# 0008_h_field_probe_1x3mm.net
KiCad netlist of a schematic drawn in EAGLE
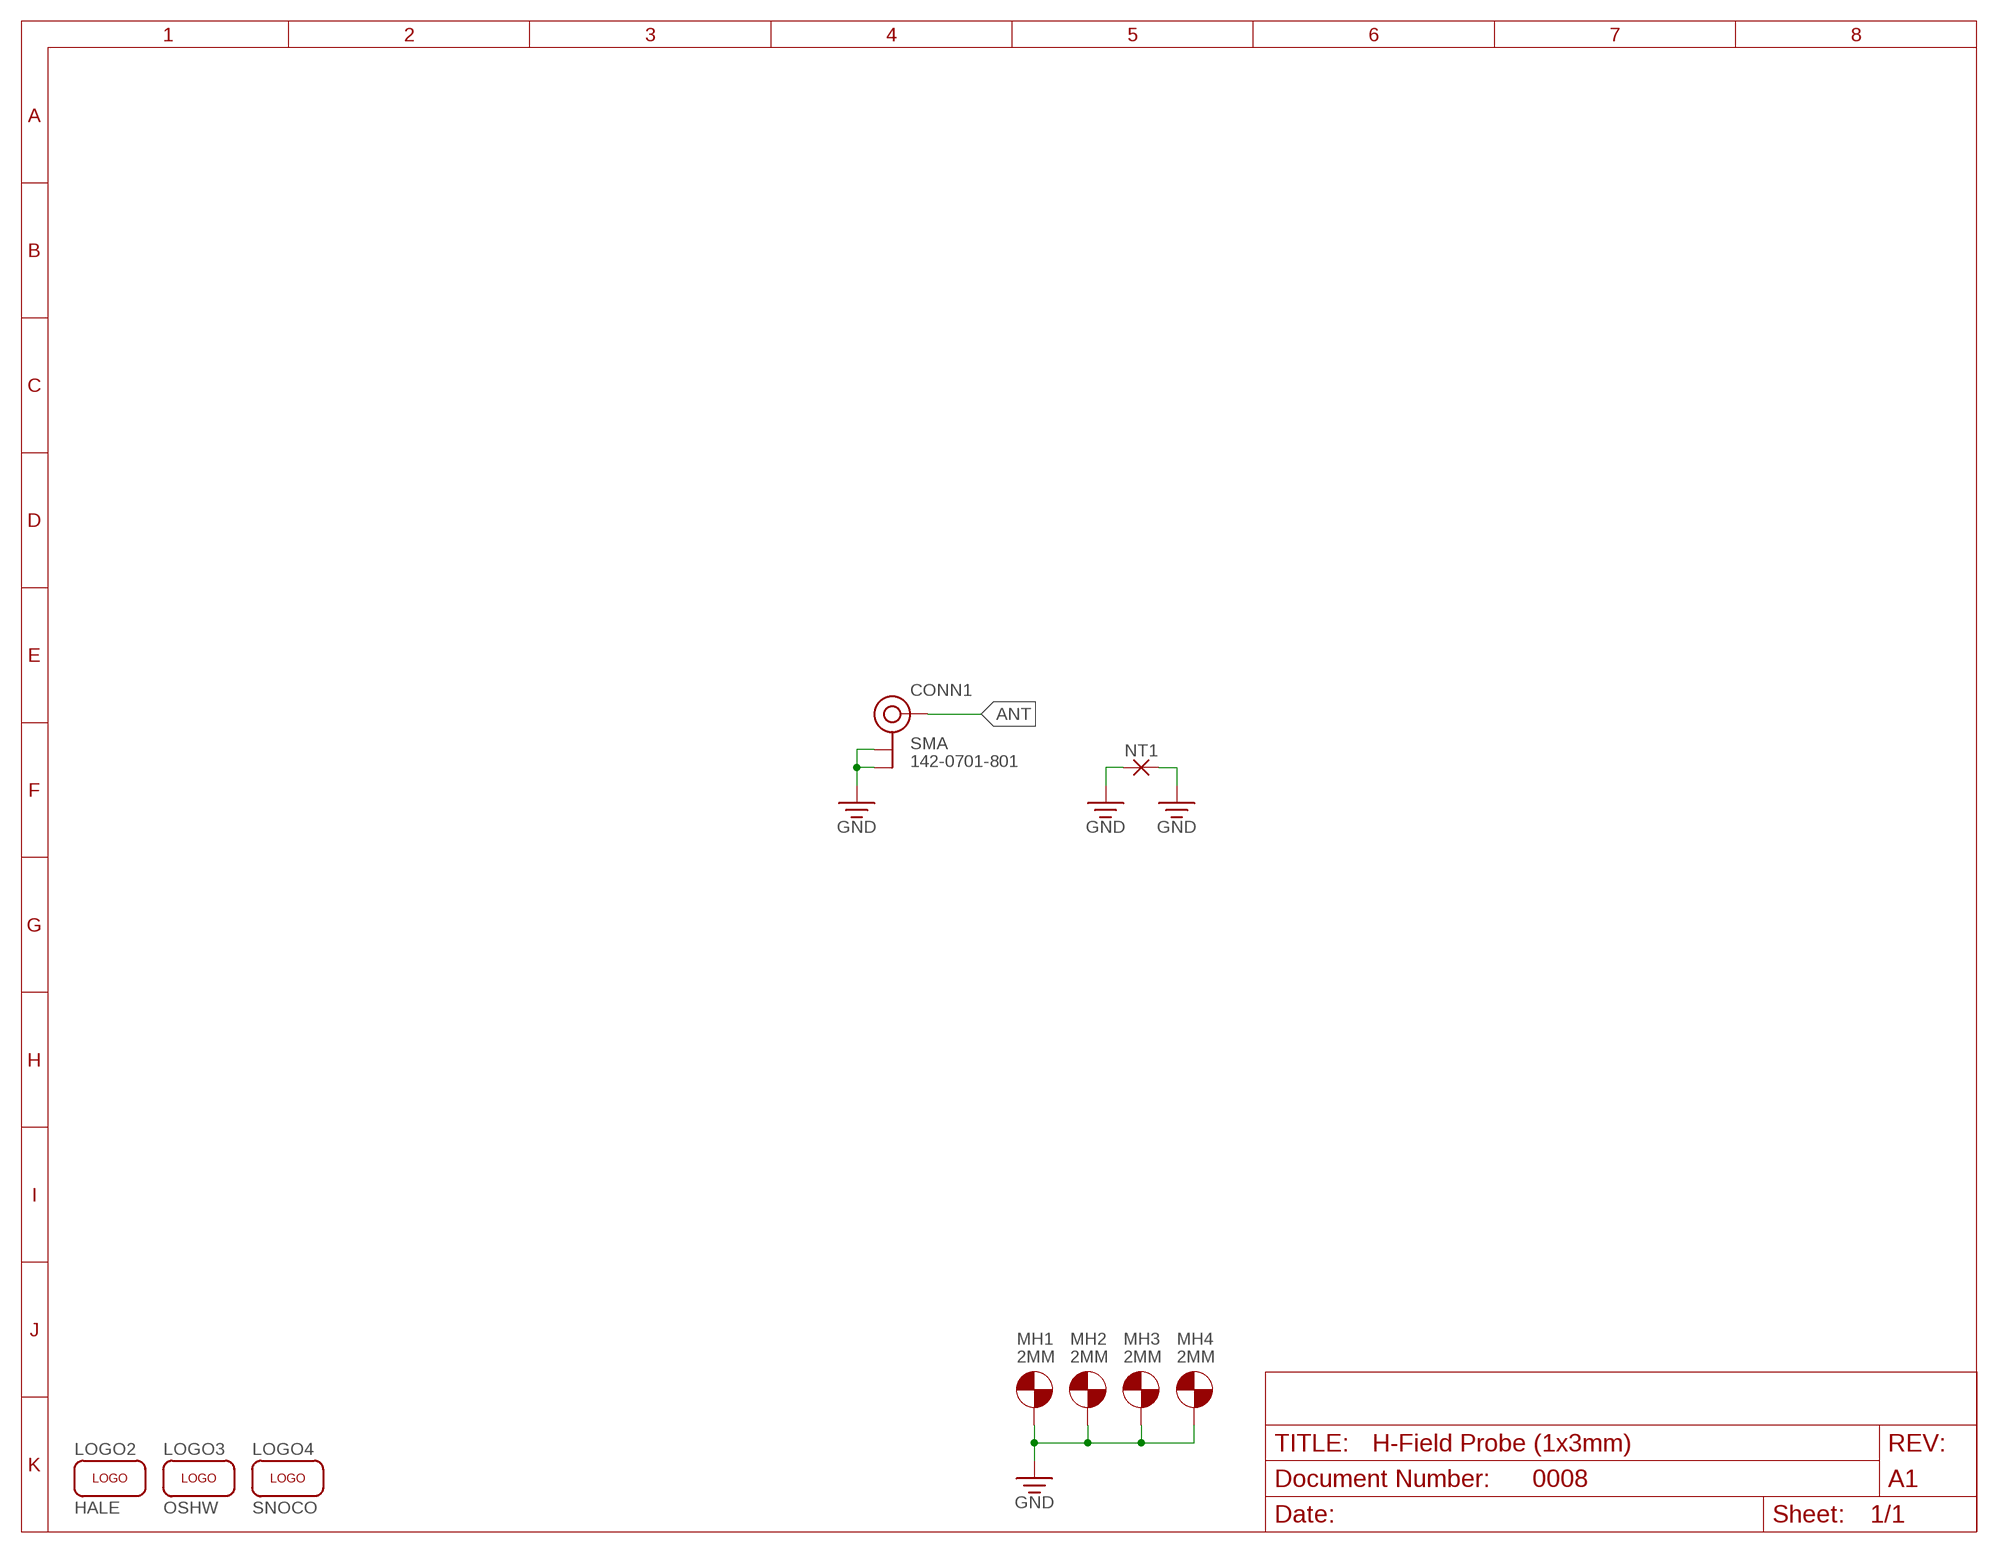
[diagram p0: schematic, sheet 1]

(export (version "E")
  (design (tool "Eeschema 10.0.6"))
  (components
    (comp (ref "CONN1")
      (value "SMA")
      (footprint "eagle-import:SMA-142-0701-801")
      (fields (field (name "MFG") "Cinch Connectivity Solutions Johnson"))
      (libsource (lib "eagle-import") (part "COAX-CONNECTOR-EDGE-SMA"))
    )
    (comp (ref "LOGO2")
      (value "HALE")
      (footprint "eagle-import:HALE-SILK-ICON")
      (libsource (lib "eagle-import") (part "LOGO-HALE"))
    )
    (comp (ref "LOGO3")
      (value "OSHW")
      (footprint "eagle-import:OSHW-SILK-ICON")
      (libsource (lib "eagle-import") (part "LOGO-OSHW"))
    )
    (comp (ref "LOGO4")
      (value "SNOCO")
      (footprint "eagle-import:SNOCO-SILK-ICON")
      (libsource (lib "eagle-import") (part "LOGO-SNOCO"))
    )
    (comp (ref "MH1")
      (value "2MM")
      (footprint "eagle-import:MH-M2-ELEC")
      (libsource (lib "eagle-import") (part "MH-ELEC-M2"))
    )
    (comp (ref "MH2")
      (value "2MM")
      (footprint "eagle-import:MH-M2-ELEC")
      (libsource (lib "eagle-import") (part "MH-ELEC-M2"))
    )
    (comp (ref "MH3")
      (value "2MM")
      (footprint "eagle-import:MH-M2-ELEC")
      (libsource (lib "eagle-import") (part "MH-ELEC-M2"))
    )
    (comp (ref "MH4")
      (value "2MM")
      (footprint "eagle-import:MH-M2-ELEC")
      (libsource (lib "eagle-import") (part "MH-ELEC-M2"))
    )
    (comp (ref "NT1")
      (value "NETTIE-VIA-TB")
      (footprint "eagle-import:NETTIE-VIA-TB")
      (libsource (lib "eagle-import") (part "NETTIE-VIA-TB"))
    )
    (comp (ref "U$2")
      (value "FRAME-8.5X11-LANDSCAPE-LET")
      (footprint "eagle-import:FRAME-8.5X11-LANDSCAPE")
      (fields (field (name "DOCNUM") "0008") (field (name "TITLE") "H-Field Probe (1x3mm)"))
      (libsource (lib "eagle-import") (part "FRAME-8.5X11-LANDSCAPE-LET"))
    )
  )
  (nets
    (net (code "1") (name "ANT") (class "Default")
      (node (ref "CONN1") (pin "2") (pinfunction "SIGNAL_2") (pintype "passive"))
    )
    (net (code "2") (name "GND") (class "Default")
      (node (ref "CONN1") (pin "1") (pinfunction "GND_1") (pintype "power_in"))
      (node (ref "CONN1") (pin "3") (pinfunction "GND_3") (pintype "power_in"))
      (node (ref "CONN1") (pin "4") (pinfunction "GND_4") (pintype "power_in"))
      (node (ref "CONN1") (pin "5") (pinfunction "GND_5") (pintype "power_in"))
      (node (ref "MH1") (pin "1") (pinfunction "1_1") (pintype "passive"))
      (node (ref "MH2") (pin "1") (pinfunction "1_1") (pintype "passive"))
      (node (ref "MH3") (pin "1") (pinfunction "1_1") (pintype "passive"))
      (node (ref "MH4") (pin "1") (pinfunction "1_1") (pintype "passive"))
      (node (ref "NT1") (pin "1") (pinfunction "1_1") (pintype "passive"))
      (node (ref "NT1") (pin "2") (pinfunction "2_2") (pintype "passive"))
    )
  )
)
